# GeorgeTry1.net
KiCad netlist of a schematic drawn in EAGLE
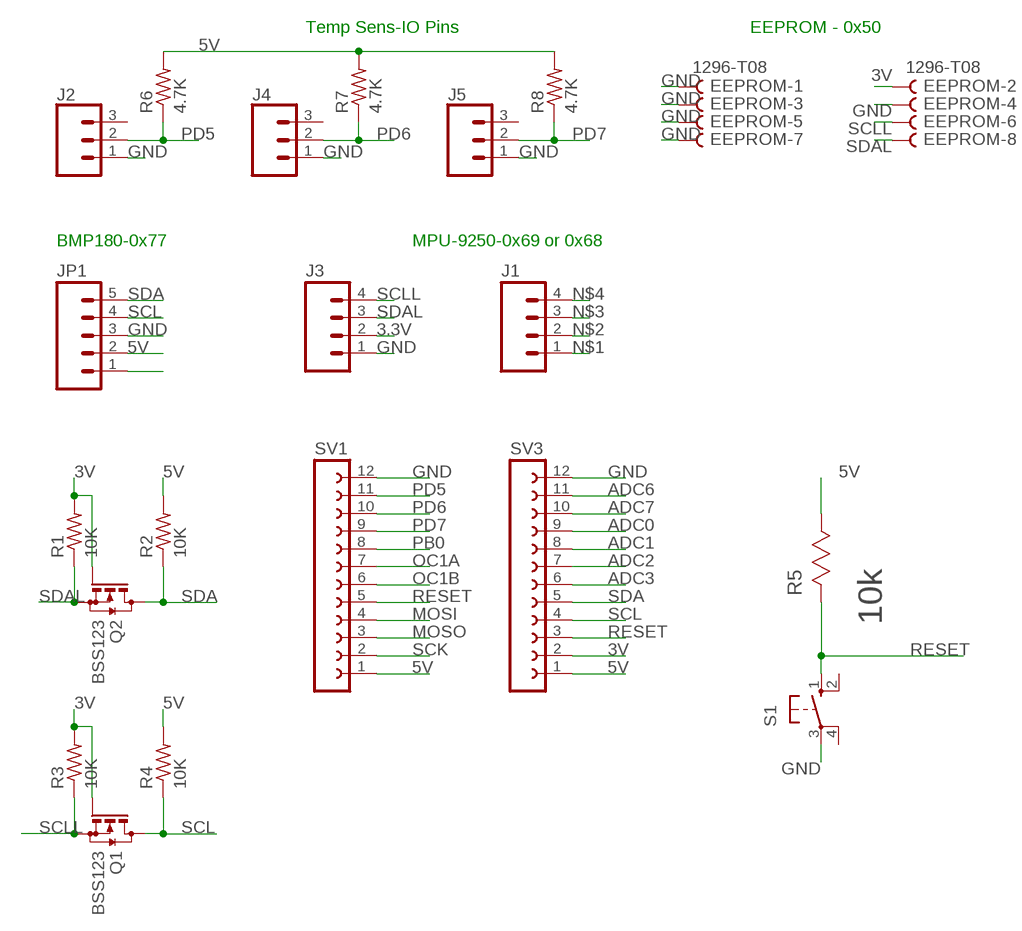
[diagram p0: schematic, sheet 1]

(export (version "E")
  (design (tool "Eeschema 10.0.6"))
  (components
    (comp (ref "EEPROM")
      (value "1296-T08")
      (footprint "eagle-import:1296-08")
      (libsource (lib "eagle-import") (part "1296-T08"))
    )
    (comp (ref "J1")
      (value "M04PTH")
      (footprint "eagle-import:1X04")
      (libsource (lib "eagle-import") (part "M04PTH"))
    )
    (comp (ref "J2")
      (value "CONN_03")
      (footprint "eagle-import:1X03")
      (libsource (lib "eagle-import") (part "CONN_03"))
    )
    (comp (ref "J3")
      (value "M04PTH")
      (footprint "eagle-import:1X04")
      (libsource (lib "eagle-import") (part "M04PTH"))
    )
    (comp (ref "J4")
      (value "CONN_03")
      (footprint "eagle-import:1X03")
      (libsource (lib "eagle-import") (part "CONN_03"))
    )
    (comp (ref "J5")
      (value "CONN_03")
      (footprint "eagle-import:1X03")
      (libsource (lib "eagle-import") (part "CONN_03"))
    )
    (comp (ref "JP1")
      (value "M05SMD2")
      (footprint "eagle-import:1X05-1MM-RA")
      (libsource (lib "eagle-import") (part "M05SMD2"))
    )
    (comp (ref "Q1")
      (value "BSS123")
      (footprint "eagle-import:SOT23")
      (libsource (lib "eagle-import") (part "BSS123"))
    )
    (comp (ref "Q2")
      (value "BSS123")
      (footprint "eagle-import:SOT23")
      (libsource (lib "eagle-import") (part "BSS123"))
    )
    (comp (ref "R1")
      (value "10K")
      (footprint "eagle-import:M1406")
      (libsource (lib "eagle-import") (part "R-US_M1406"))
    )
    (comp (ref "R2")
      (value "10K")
      (footprint "eagle-import:M1406")
      (libsource (lib "eagle-import") (part "R-US_M1406"))
    )
    (comp (ref "R3")
      (value "10K")
      (footprint "eagle-import:M1406")
      (libsource (lib "eagle-import") (part "R-US_M1406"))
    )
    (comp (ref "R4")
      (value "10K")
      (footprint "eagle-import:M1406")
      (libsource (lib "eagle-import") (part "R-US_M1406"))
    )
    (comp (ref "R5")
      (value "10k")
      (footprint "eagle-import:RESC2013X65N")
      (fields (field (name "MPN") "CRCW08051M00JNEA") (field (name "TOLERANCE") "± 5.0 %"))
      (libsource (lib "eagle-import") (part "CRCW08051M00JNEA"))
    )
    (comp (ref "R6")
      (value "4.7K")
      (footprint "eagle-import:M1406")
      (libsource (lib "eagle-import") (part "R-US_M1406"))
    )
    (comp (ref "R7")
      (value "4.7K")
      (footprint "eagle-import:M1406")
      (libsource (lib "eagle-import") (part "R-US_M1406"))
    )
    (comp (ref "R8")
      (value "4.7K")
      (footprint "eagle-import:M1406")
      (libsource (lib "eagle-import") (part "R-US_M1406"))
    )
    (comp (ref "S1")
      (value "10-XX")
      (footprint "eagle-import:B3F-10XX")
      (fields (field (name "MPN") "B3F-1000"))
      (libsource (lib "eagle-import") (part "10-XX"))
    )
    (comp (ref "SV1")
      (value "FE12-1")
      (footprint "eagle-import:FE12")
      (libsource (lib "eagle-import") (part "FE12-1"))
    )
    (comp (ref "SV3")
      (value "FE12-1")
      (footprint "eagle-import:FE12")
      (libsource (lib "eagle-import") (part "FE12-1"))
    )
  )
  (nets
    (net (code "1") (name "/3.3V") (class "Default")
      (node (ref "J3") (pin "2") (pinfunction "2_2") (pintype "passive"))
    )
    (net (code "2") (name "/3V") (class "Default")
      (node (ref "EEPROM") (pin "2") (pinfunction "B_2") (pintype "passive"))
      (node (ref "Q1") (pin "1") (pinfunction "G_1") (pintype "passive"))
      (node (ref "Q2") (pin "1") (pinfunction "G_1") (pintype "passive"))
      (node (ref "R1") (pin "2") (pinfunction "2_2") (pintype "passive"))
      (node (ref "R3") (pin "2") (pinfunction "2_2") (pintype "passive"))
      (node (ref "SV3") (pin "2") (pinfunction "2_2") (pintype "passive"))
    )
    (net (code "3") (name "/5V") (class "Default")
      (node (ref "JP1") (pin "2") (pinfunction "2_2") (pintype "passive"))
      (node (ref "R2") (pin "2") (pinfunction "2_2") (pintype "passive"))
      (node (ref "R4") (pin "2") (pinfunction "2_2") (pintype "passive"))
      (node (ref "R5") (pin "1") (pinfunction "1_1") (pintype "passive"))
      (node (ref "R6") (pin "2") (pinfunction "2_2") (pintype "passive"))
      (node (ref "R7") (pin "2") (pinfunction "2_2") (pintype "passive"))
      (node (ref "R8") (pin "2") (pinfunction "2_2") (pintype "passive"))
      (node (ref "SV1") (pin "1") (pinfunction "1_1") (pintype "passive"))
      (node (ref "SV3") (pin "1") (pinfunction "1_1") (pintype "passive"))
    )
    (net (code "4") (name "/ADC0") (class "Default")
      (node (ref "SV3") (pin "9") (pinfunction "9_9") (pintype "passive"))
    )
    (net (code "5") (name "/ADC1") (class "Default")
      (node (ref "SV3") (pin "8") (pinfunction "8_8") (pintype "passive"))
    )
    (net (code "6") (name "/ADC2") (class "Default")
      (node (ref "SV3") (pin "7") (pinfunction "7_7") (pintype "passive"))
    )
    (net (code "7") (name "/ADC3") (class "Default")
      (node (ref "SV3") (pin "6") (pinfunction "6_6") (pintype "passive"))
    )
    (net (code "8") (name "/ADC6") (class "Default")
      (node (ref "SV3") (pin "11") (pinfunction "11_11") (pintype "passive"))
    )
    (net (code "9") (name "/ADC7") (class "Default")
      (node (ref "SV3") (pin "10") (pinfunction "10_10") (pintype "passive"))
    )
    (net (code "10") (name "/GND") (class "Default")
      (node (ref "EEPROM") (pin "1") (pinfunction "B_1") (pintype "passive"))
      (node (ref "EEPROM") (pin "3") (pinfunction "B_3") (pintype "passive"))
      (node (ref "EEPROM") (pin "4") (pinfunction "B_4") (pintype "passive"))
      (node (ref "EEPROM") (pin "5") (pinfunction "B_5") (pintype "passive"))
      (node (ref "EEPROM") (pin "7") (pinfunction "B_7") (pintype "passive"))
      (node (ref "J2") (pin "1") (pinfunction "1_1") (pintype "passive"))
      (node (ref "J3") (pin "1") (pinfunction "1_1") (pintype "passive"))
      (node (ref "J4") (pin "1") (pinfunction "1_1") (pintype "passive"))
      (node (ref "J5") (pin "1") (pinfunction "1_1") (pintype "passive"))
      (node (ref "JP1") (pin "3") (pinfunction "3_3") (pintype "passive"))
      (node (ref "S1") (pin "3") (pinfunction "P_3") (pintype "passive"))
      (node (ref "SV1") (pin "12") (pinfunction "12_12") (pintype "passive"))
      (node (ref "SV3") (pin "12") (pinfunction "12_12") (pintype "passive"))
    )
    (net (code "11") (name "/MOSI") (class "Default")
      (node (ref "SV1") (pin "4") (pinfunction "4_4") (pintype "passive"))
    )
    (net (code "12") (name "/MOSO") (class "Default")
      (node (ref "SV1") (pin "3") (pinfunction "3_3") (pintype "passive"))
    )
    (net (code "13") (name "/N$1") (class "Default")
      (node (ref "J1") (pin "1") (pinfunction "1_1") (pintype "passive"))
    )
    (net (code "14") (name "/N$2") (class "Default")
      (node (ref "J1") (pin "2") (pinfunction "2_2") (pintype "passive"))
    )
    (net (code "15") (name "/N$3") (class "Default")
      (node (ref "J1") (pin "3") (pinfunction "3_3") (pintype "passive"))
    )
    (net (code "16") (name "/N$4") (class "Default")
      (node (ref "J1") (pin "4") (pinfunction "4_4") (pintype "passive"))
    )
    (net (code "17") (name "/OC1A") (class "Default")
      (node (ref "SV1") (pin "7") (pinfunction "7_7") (pintype "passive"))
    )
    (net (code "18") (name "/OC1B") (class "Default")
      (node (ref "SV1") (pin "6") (pinfunction "6_6") (pintype "passive"))
    )
    (net (code "19") (name "/PB0") (class "Default")
      (node (ref "SV1") (pin "8") (pinfunction "8_8") (pintype "passive"))
    )
    (net (code "20") (name "/PD5") (class "Default")
      (node (ref "J2") (pin "2") (pinfunction "2_2") (pintype "passive"))
      (node (ref "R6") (pin "1") (pinfunction "1_1") (pintype "passive"))
      (node (ref "SV1") (pin "11") (pinfunction "11_11") (pintype "passive"))
    )
    (net (code "21") (name "/PD6") (class "Default")
      (node (ref "J4") (pin "2") (pinfunction "2_2") (pintype "passive"))
      (node (ref "R7") (pin "1") (pinfunction "1_1") (pintype "passive"))
      (node (ref "SV1") (pin "10") (pinfunction "10_10") (pintype "passive"))
    )
    (net (code "22") (name "/PD7") (class "Default")
      (node (ref "J5") (pin "2") (pinfunction "2_2") (pintype "passive"))
      (node (ref "R8") (pin "1") (pinfunction "1_1") (pintype "passive"))
      (node (ref "SV1") (pin "9") (pinfunction "9_9") (pintype "passive"))
    )
    (net (code "23") (name "/RESET") (class "Default")
      (node (ref "R5") (pin "2") (pinfunction "2_2") (pintype "passive"))
      (node (ref "S1") (pin "1") (pinfunction "S_1") (pintype "passive"))
      (node (ref "SV1") (pin "5") (pinfunction "5_5") (pintype "passive"))
      (node (ref "SV3") (pin "3") (pinfunction "3_3") (pintype "passive"))
    )
    (net (code "24") (name "/SCK") (class "Default")
      (node (ref "SV1") (pin "2") (pinfunction "2_2") (pintype "passive"))
    )
    (net (code "25") (name "/SCL") (class "Default")
      (node (ref "JP1") (pin "4") (pinfunction "4_4") (pintype "passive"))
      (node (ref "Q1") (pin "3") (pinfunction "D_3") (pintype "passive"))
      (node (ref "R4") (pin "1") (pinfunction "1_1") (pintype "passive"))
      (node (ref "SV3") (pin "4") (pinfunction "4_4") (pintype "passive"))
    )
    (net (code "26") (name "/SCLL") (class "Default")
      (node (ref "EEPROM") (pin "6") (pinfunction "B_6") (pintype "passive"))
      (node (ref "J3") (pin "4") (pinfunction "4_4") (pintype "passive"))
      (node (ref "Q1") (pin "2") (pinfunction "S_2") (pintype "passive"))
      (node (ref "R3") (pin "1") (pinfunction "1_1") (pintype "passive"))
    )
    (net (code "27") (name "/SDA") (class "Default")
      (node (ref "JP1") (pin "5") (pinfunction "5_5") (pintype "passive"))
      (node (ref "Q2") (pin "3") (pinfunction "D_3") (pintype "passive"))
      (node (ref "R2") (pin "1") (pinfunction "1_1") (pintype "passive"))
      (node (ref "SV3") (pin "5") (pinfunction "5_5") (pintype "passive"))
    )
    (net (code "28") (name "/SDAL") (class "Default")
      (node (ref "EEPROM") (pin "8") (pinfunction "B_8") (pintype "passive"))
      (node (ref "J3") (pin "3") (pinfunction "3_3") (pintype "passive"))
      (node (ref "Q2") (pin "2") (pinfunction "S_2") (pintype "passive"))
      (node (ref "R1") (pin "1") (pinfunction "1_1") (pintype "passive"))
    )
    (net (code "29") (name "unconnected-(J2-Pad3)") (class "Default")
      (node (ref "J2") (pin "3") (pinfunction "3_3") (pintype "passive"))
    )
    (net (code "30") (name "unconnected-(J4-Pad3)") (class "Default")
      (node (ref "J4") (pin "3") (pinfunction "3_3") (pintype "passive"))
    )
    (net (code "31") (name "unconnected-(J5-Pad3)") (class "Default")
      (node (ref "J5") (pin "3") (pinfunction "3_3") (pintype "passive"))
    )
    (net (code "32") (name "unconnected-(JP1-Pad1)") (class "Default")
      (node (ref "JP1") (pin "1") (pinfunction "1_1") (pintype "passive"))
    )
    (net (code "33") (name "unconnected-(S1-P1-Pad4)") (class "Default")
      (node (ref "S1") (pin "4") (pinfunction "P1_4") (pintype "passive"))
    )
    (net (code "34") (name "unconnected-(S1-S1-Pad2)") (class "Default")
      (node (ref "S1") (pin "2") (pinfunction "S1_2") (pintype "passive"))
    )
  )
)
